# H1N1.net
KiCad netlist of a schematic drawn in Altium Designer
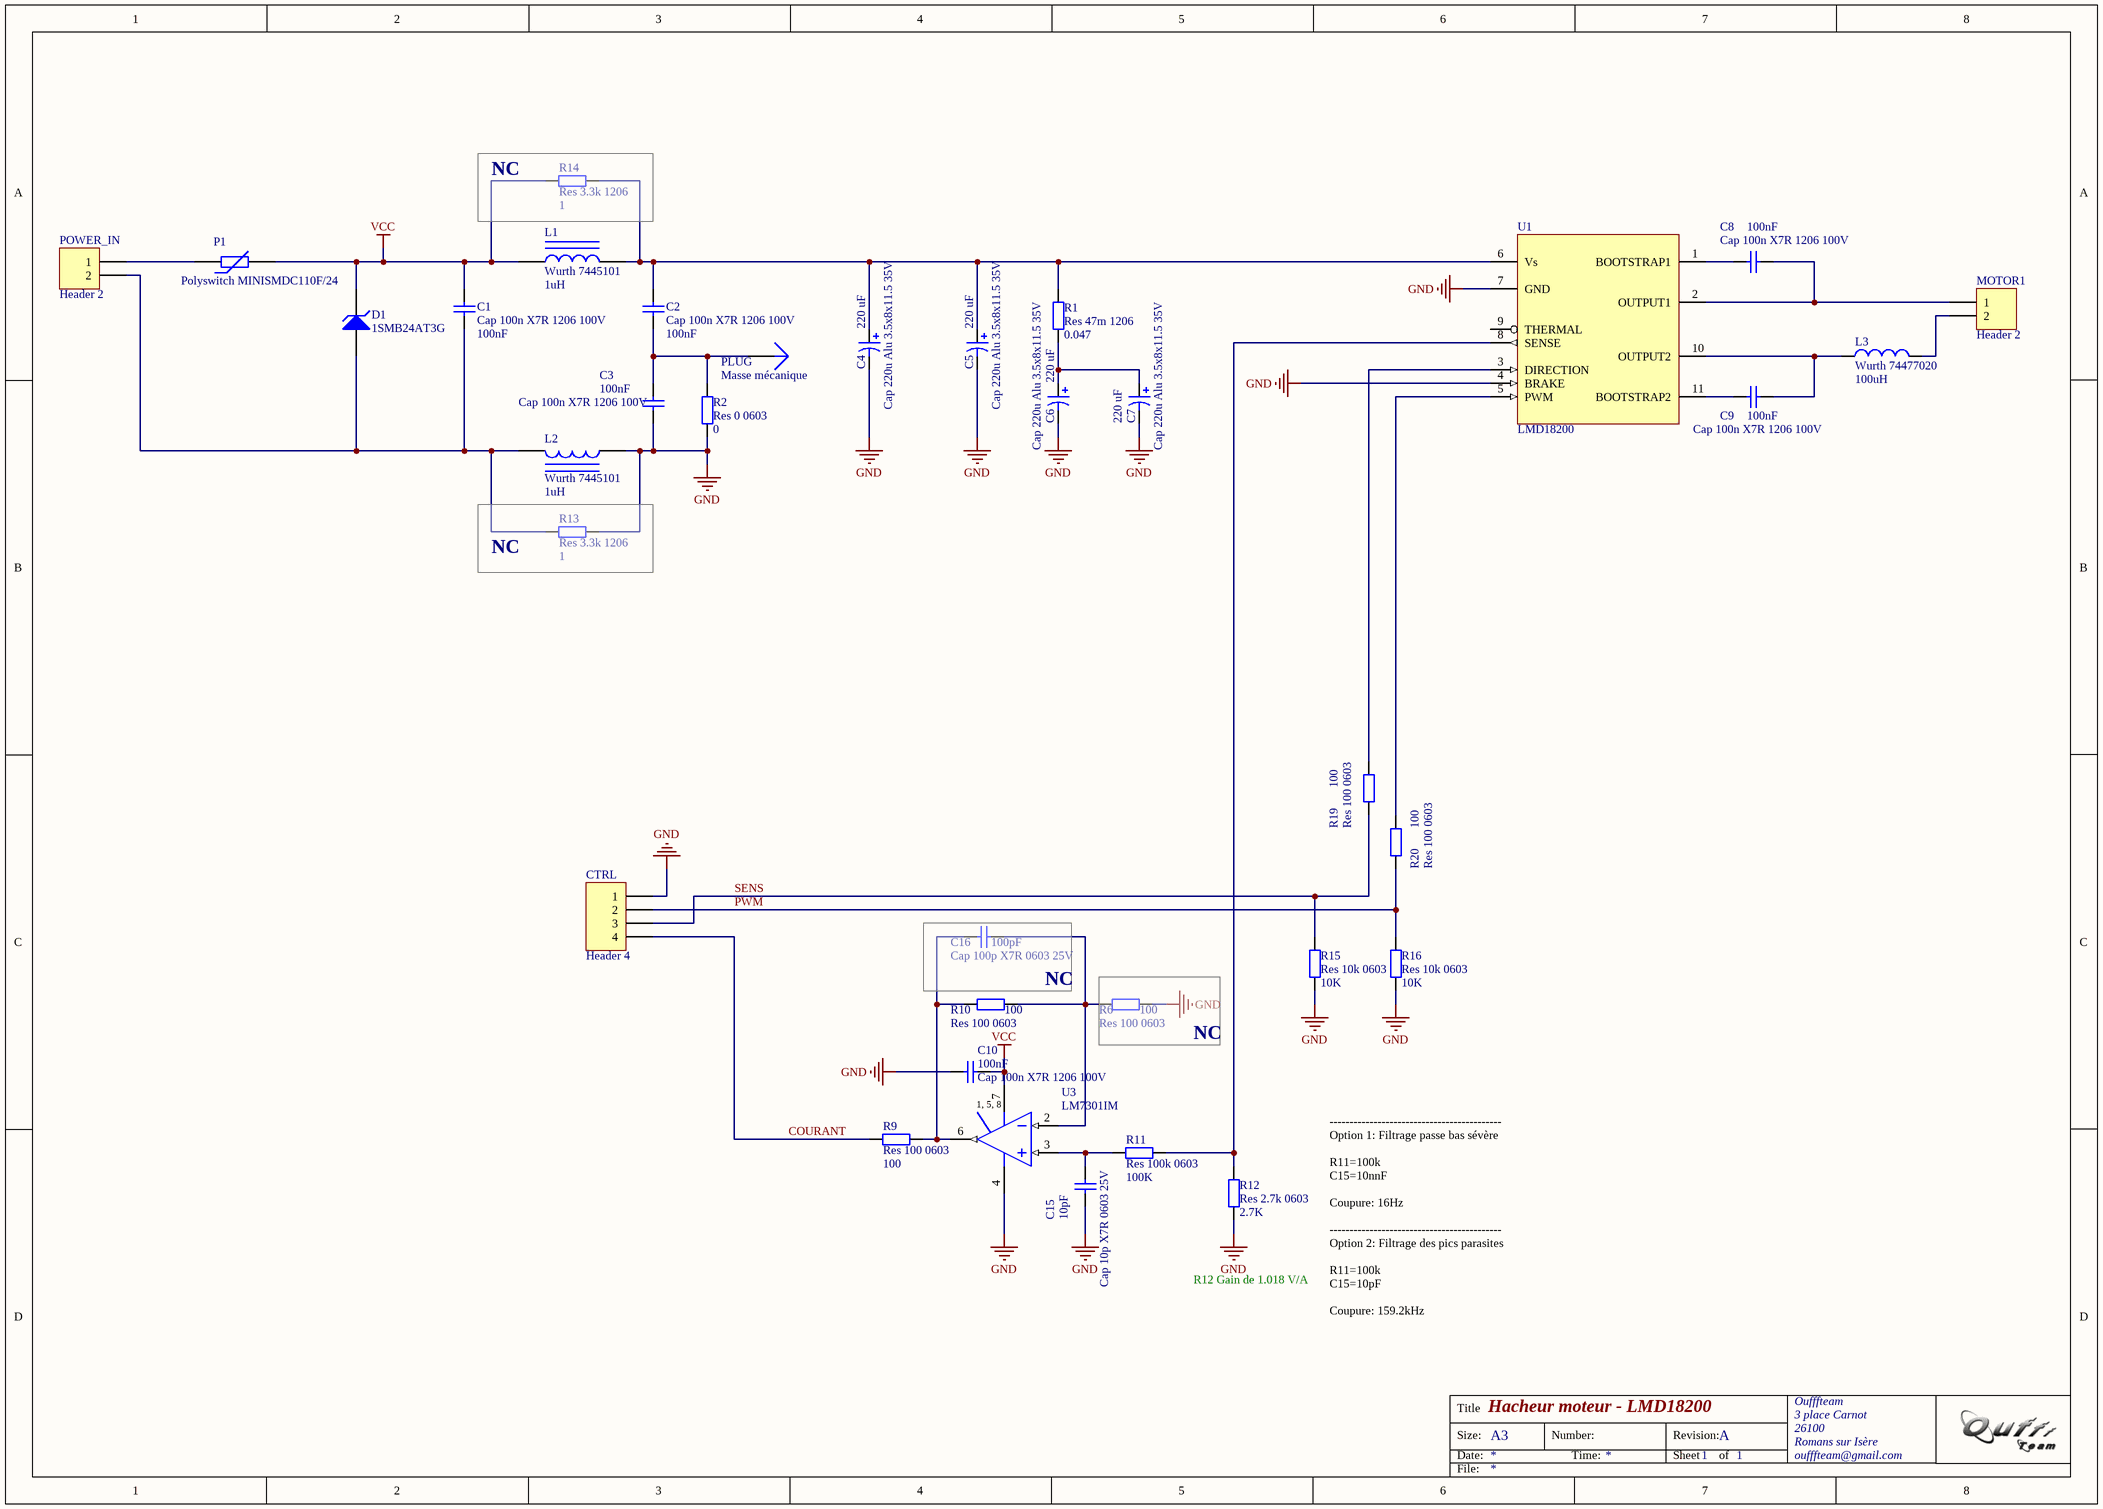
[diagram p0: H1N1.SchDoc]

(export (version "E")
  (design (tool "Eeschema 10.0.6"))
  (components
    (comp (ref "C1")
      (value "Cap 100n X7R 1206 100V")
      (footprint "3216[1206]")
      (description "Capacitor")
      (fields (field (name "ALTIUM_VALUE") "100nF") (field (name "PUBLISHER") "Altium Limited"))
      (libsource (lib "Miscellaneous Devices") (part "Cap"))
    )
    (comp (ref "C2")
      (value "Cap 100n X7R 1206 100V")
      (footprint "3216[1206]")
      (description "Capacitor")
      (fields (field (name "ALTIUM_VALUE") "100nF") (field (name "PUBLISHER") "Altium Limited"))
      (libsource (lib "Miscellaneous Devices") (part "Cap"))
    )
    (comp (ref "C3")
      (value "Cap 100n X7R 1206 100V")
      (footprint "3216[1206]")
      (description "Capacitor")
      (fields (field (name "ALTIUM_VALUE") "100nF") (field (name "PUBLISHER") "Altium Limited"))
      (libsource (lib "Miscellaneous Devices") (part "Cap"))
    )
    (comp (ref "C4")
      (value "Cap 220u Alu 3.5x8x11.5 35V")
      (footprint "CAPPR3.5-8X11.5")
      (description "Polarized Capacitor (Radial)")
      (fields (field (name "ALTIUM_VALUE") "220 uF") (field (name "PUBLISHER") "Altium Limited"))
      (libsource (lib "Miscellaneous Devices") (part "Cap Pol1"))
    )
    (comp (ref "C5")
      (value "Cap 220u Alu 3.5x8x11.5 35V")
      (footprint "CAPPR3.5-8X11.5")
      (description "Polarized Capacitor (Radial)")
      (fields (field (name "ALTIUM_VALUE") "220 uF") (field (name "PUBLISHER") "Altium Limited"))
      (libsource (lib "Miscellaneous Devices") (part "Cap Pol1"))
    )
    (comp (ref "C6")
      (value "Cap 220u Alu 3.5x8x11.5 35V")
      (footprint "CAPPR3.5-8X11.5")
      (description "Polarized Capacitor (Radial)")
      (fields (field (name "ALTIUM_VALUE") "220 uF") (field (name "PUBLISHER") "Altium Limited"))
      (libsource (lib "Miscellaneous Devices") (part "Cap Pol1"))
    )
    (comp (ref "C7")
      (value "Cap 220u Alu 3.5x8x11.5 35V")
      (footprint "CAPPR3.5-8X11.5")
      (description "Polarized Capacitor (Radial)")
      (fields (field (name "ALTIUM_VALUE") "220 uF") (field (name "PUBLISHER") "Altium Limited"))
      (libsource (lib "Miscellaneous Devices") (part "Cap Pol1"))
    )
    (comp (ref "C8")
      (value "Cap 100n X7R 1206 100V")
      (footprint "3216[1206]")
      (description "Capacitor")
      (fields (field (name "ALTIUM_VALUE") "100nF") (field (name "PUBLISHER") "Altium Limited"))
      (libsource (lib "Miscellaneous Devices") (part "Cap"))
    )
    (comp (ref "C9")
      (value "Cap 100n X7R 1206 100V")
      (footprint "3216[1206]")
      (description "Capacitor")
      (fields (field (name "ALTIUM_VALUE") "100nF") (field (name "PUBLISHER") "Altium Limited"))
      (libsource (lib "Miscellaneous Devices") (part "Cap"))
    )
    (comp (ref "C10")
      (value "Cap 100n X7R 1206 100V")
      (footprint "3216[1206]")
      (description "Capacitor")
      (fields (field (name "ALTIUM_VALUE") "100nF") (field (name "PUBLISHER") "Altium Limited"))
      (libsource (lib "Miscellaneous Devices") (part "Cap"))
    )
    (comp (ref "C15")
      (value "Cap 10p X7R 0603 25V")
      (footprint "1608[0603]")
      (description "Capacitor")
      (fields (field (name "ALTIUM_VALUE") "10pF") (field (name "PUBLISHER") "Altium Limited"))
      (libsource (lib "Miscellaneous Devices") (part "Cap"))
    )
    (comp (ref "C16")
      (value "Cap 100p X7R 0603 25V")
      (footprint "1608[0603]")
      (description "Capacitor")
      (fields (field (name "ALTIUM_VALUE") "100pF") (field (name "PUBLISHER") "Altium Limited"))
      (libsource (lib "Miscellaneous Devices") (part "Cap"))
    )
    (comp (ref "CTRL")
      (value "Header 4")
      (footprint "HDR1X4")
      (description "Header, 4-Pin")
      (fields (field (name "PUBLISHER") "Altium Limited"))
      (libsource (lib "Miscellaneous Connectors") (part "Header 4"))
    )
    (comp (ref "D1")
      (value "1SMB24AT3G")
      (footprint "SMB")
      (description "Zener Diode")
      (fields (field (name "PUBLISHER") "Altium Limited"))
      (libsource (lib "Miscellaneous Devices") (part "D Zener"))
    )
    (comp (ref "L1")
      (value "Wurth 7445101")
      (footprint "7445101")
      (description "Magnetic-Core Inductor")
      (fields (field (name "ALTIUM_VALUE") "1uH") (field (name "PUBLISHER") "Altium Limited"))
      (libsource (lib "Miscellaneous Devices") (part "Inductor Iron"))
    )
    (comp (ref "L2")
      (value "Wurth 7445101")
      (footprint "7445101")
      (description "Magnetic-Core Inductor")
      (fields (field (name "ALTIUM_VALUE") "1uH") (field (name "PUBLISHER") "Altium Limited"))
      (libsource (lib "Miscellaneous Devices") (part "Inductor Iron"))
    )
    (comp (ref "L3")
      (value "Wurth 74477020")
      (footprint "74477020")
      (description "Inductor")
      (fields (field (name "ALTIUM_VALUE") "100uH") (field (name "PUBLISHER") "Altium Limited"))
      (libsource (lib "Miscellaneous Devices") (part "Inductor"))
    )
    (comp (ref "MOTOR1")
      (value "Header 2")
      (footprint "Bornier 3.85")
      (description "Header, 2-Pin")
      (fields (field (name "PUBLISHER") "Altium Limited"))
      (libsource (lib "Miscellaneous Connectors") (part "Header 2"))
    )
    (comp (ref "P1")
      (value "Polyswitch MINISMDC110F/24")
      (footprint "1812")
      (description "Varistor (Voltage-Sensitive Resistor)")
      (fields (field (name "PUBLISHER") "Altium Limited"))
      (libsource (lib "Miscellaneous Devices") (part "Res Varistor"))
    )
    (comp (ref "PLUG")
      (value "Masse mécanique")
      (footprint "PIN1")
      (description "Plug")
      (fields (field (name "PUBLISHER") "Altium Limited"))
      (libsource (lib "Miscellaneous Connectors") (part "Plug"))
    )
    (comp (ref "POWER_IN")
      (value "Header 2")
      (footprint "Bornier 3.85")
      (description "Header, 2-Pin")
      (fields (field (name "PUBLISHER") "Altium Limited"))
      (libsource (lib "") (part "Header 2_1"))
    )
    (comp (ref "R1")
      (value "Res 47m 1206")
      (footprint "3216[1206]")
      (description "Resistor")
      (fields (field (name "ALTIUM_VALUE") "0.047") (field (name "PUBLISHER") "Altium Limited"))
      (libsource (lib "") (part "Res2_1"))
    )
    (comp (ref "R2")
      (value "Res 0 0603")
      (footprint "1608[0603]")
      (description "Resistor")
      (fields (field (name "ALTIUM_VALUE") "0") (field (name "PUBLISHER") "Altium Limited"))
      (libsource (lib "") (part "Res2_1"))
    )
    (comp (ref "R6")
      (value "Res 100 0603")
      (footprint "1608[0603]")
      (description "Resistor")
      (fields (field (name "ALTIUM_VALUE") "100") (field (name "PUBLISHER") "Altium Limited"))
      (libsource (lib "Miscellaneous Devices") (part "Res2"))
    )
    (comp (ref "R9")
      (value "Res 100 0603")
      (footprint "1608[0603]")
      (description "Resistor")
      (fields (field (name "ALTIUM_VALUE") "100") (field (name "PUBLISHER") "Altium Limited"))
      (libsource (lib "Miscellaneous Devices") (part "Res2"))
    )
    (comp (ref "R10")
      (value "Res 100 0603")
      (footprint "1608[0603]")
      (description "Resistor")
      (fields (field (name "ALTIUM_VALUE") "100") (field (name "PUBLISHER") "Altium Limited"))
      (libsource (lib "Miscellaneous Devices") (part "Res2"))
    )
    (comp (ref "R11")
      (value "Res 100k 0603")
      (footprint "1608[0603]")
      (description "Resistor")
      (fields (field (name "ALTIUM_VALUE") "100K") (field (name "PUBLISHER") "Altium Limited"))
      (libsource (lib "") (part "Res2_2"))
    )
    (comp (ref "R12")
      (value "Res 2.7k 0603")
      (footprint "1608[0603]")
      (description "Resistor")
      (fields (field (name "ALTIUM_VALUE") "2.7K") (field (name "PUBLISHER") "Altium Limited"))
      (libsource (lib "") (part "Res2_1"))
    )
    (comp (ref "R13")
      (value "Res 3.3k 1206")
      (footprint "3216[1206]")
      (description "Resistor")
      (fields (field (name "ALTIUM_VALUE") "1") (field (name "PUBLISHER") "Altium Limited"))
      (libsource (lib "Miscellaneous Devices") (part "Res2"))
    )
    (comp (ref "R14")
      (value "Res 3.3k 1206")
      (footprint "3216[1206]")
      (description "Resistor")
      (fields (field (name "ALTIUM_VALUE") "1") (field (name "PUBLISHER") "Altium Limited"))
      (libsource (lib "Miscellaneous Devices") (part "Res2"))
    )
    (comp (ref "R15")
      (value "Res 10k 0603")
      (footprint "1608[0603]")
      (description "Resistor")
      (fields (field (name "ALTIUM_VALUE") "10K") (field (name "PUBLISHER") "Altium Limited"))
      (libsource (lib "") (part "Res2_1"))
    )
    (comp (ref "R16")
      (value "Res 10k 0603")
      (footprint "1608[0603]")
      (description "Resistor")
      (fields (field (name "ALTIUM_VALUE") "10K") (field (name "PUBLISHER") "Altium Limited"))
      (libsource (lib "") (part "Res2_1"))
    )
    (comp (ref "R19")
      (value "Res 100 0603")
      (footprint "1608[0603]")
      (description "Resistor")
      (fields (field (name "ALTIUM_VALUE") "100") (field (name "PUBLISHER") "Altium Limited"))
      (libsource (lib "") (part "Res2_1"))
    )
    (comp (ref "R20")
      (value "Res 100 0603")
      (footprint "1608[0603]")
      (description "Resistor")
      (fields (field (name "ALTIUM_VALUE") "100") (field (name "PUBLISHER") "Altium Limited"))
      (libsource (lib "") (part "Res2_1"))
    )
    (comp (ref "U1")
      (value "LMD18200")
      (footprint "LMD18200")
      (description "3A, 55V H-Bridge")
      (libsource (lib "NSC Interface DC Motor Controller Driver") (part "LMD18200"))
    )
    (comp (ref "U3")
      (value "LM7301IM")
      (footprint "M08A_M")
      (description "Low-Power, 4MHZ GBW, Rail-to-Rail Input-Output Operational Amplifier in TinyPak Package")
      (fields (field (name "PUBLISHER") "Altium Limited"))
      (libsource (lib "NSC Operational Amplifier") (part "LM7301IM"))
    )
  )
  (nets
    (net (code "1") (name "/COURANT") (class "Default")
      (node (ref "CTRL") (pin "4") (pinfunction "4_4") (pintype "passive"))
      (node (ref "R9") (pin "1") (pinfunction "1_1") (pintype "passive"))
    )
    (net (code "2") (name "/PWM") (class "Default")
      (node (ref "CTRL") (pin "2") (pinfunction "2_2") (pintype "passive"))
      (node (ref "R16") (pin "2") (pinfunction "2_2") (pintype "passive"))
      (node (ref "R20") (pin "1") (pinfunction "1_1") (pintype "passive"))
    )
    (net (code "3") (name "/SENS") (class "Default")
      (node (ref "CTRL") (pin "3") (pinfunction "3_3") (pintype "passive"))
      (node (ref "R15") (pin "2") (pinfunction "2_2") (pintype "passive"))
      (node (ref "R19") (pin "1") (pinfunction "1_1") (pintype "passive"))
    )
    (net (code "4") (name "GND") (class "Default")
      (node (ref "C10") (pin "1") (pinfunction "1_1") (pintype "passive"))
      (node (ref "C15") (pin "1") (pinfunction "1_1") (pintype "passive"))
      (node (ref "C3") (pin "1") (pinfunction "1_1") (pintype "passive"))
      (node (ref "C4") (pin "2") (pinfunction "2_2") (pintype "passive"))
      (node (ref "C5") (pin "2") (pinfunction "2_2") (pintype "passive"))
      (node (ref "C6") (pin "2") (pinfunction "2_2") (pintype "passive"))
      (node (ref "C7") (pin "2") (pinfunction "2_2") (pintype "passive"))
      (node (ref "CTRL") (pin "1") (pinfunction "1_1") (pintype "passive"))
      (node (ref "L2") (pin "1") (pinfunction "1_1") (pintype "passive"))
      (node (ref "R12") (pin "1") (pinfunction "1_1") (pintype "passive"))
      (node (ref "R13") (pin "2") (pinfunction "2_2") (pintype "passive"))
      (node (ref "R15") (pin "1") (pinfunction "1_1") (pintype "passive"))
      (node (ref "R16") (pin "1") (pinfunction "1_1") (pintype "passive"))
      (node (ref "R2") (pin "1") (pinfunction "1_1") (pintype "passive"))
      (node (ref "R6") (pin "2") (pinfunction "2_2") (pintype "passive"))
      (node (ref "U1") (pin "4") (pinfunction "BRAKE_4") (pintype "input"))
      (node (ref "U1") (pin "7") (pinfunction "GND_7") (pintype "power_in"))
      (node (ref "U3") (pin "4") (pinfunction "V-_4") (pintype "power_in"))
    )
    (net (code "5") (name "Net-(C2-Pad1)") (class "Default")
      (node (ref "C2") (pin "1") (pinfunction "1_1") (pintype "passive"))
      (node (ref "C3") (pin "2") (pinfunction "2_2") (pintype "passive"))
      (node (ref "PLUG") (pin "1") (pinfunction "1_1") (pintype "passive"))
      (node (ref "R2") (pin "2") (pinfunction "2_2") (pintype "passive"))
    )
    (net (code "6") (name "Net-(C6-Pad1)") (class "Default")
      (node (ref "C6") (pin "1") (pinfunction "1_1") (pintype "passive"))
      (node (ref "C7") (pin "1") (pinfunction "1_1") (pintype "passive"))
      (node (ref "R1") (pin "1") (pinfunction "1_1") (pintype "passive"))
    )
    (net (code "7") (name "Net-(D1-A)") (class "Default")
      (node (ref "C1") (pin "1") (pinfunction "1_1") (pintype "passive"))
      (node (ref "D1") (pin "1") (pinfunction "A_1") (pintype "passive"))
      (node (ref "L2") (pin "2") (pinfunction "2_2") (pintype "passive"))
      (node (ref "POWER_IN") (pin "2") (pinfunction "2_2") (pintype "passive"))
      (node (ref "R13") (pin "1") (pinfunction "1_1") (pintype "passive"))
    )
    (net (code "8") (name "Net-(L3-Pad2)") (class "Default")
      (node (ref "L3") (pin "2") (pinfunction "2_2") (pintype "passive"))
      (node (ref "MOTOR1") (pin "2") (pinfunction "2_2") (pintype "passive"))
    )
    (net (code "9") (name "Net-(P1-Pad1)") (class "Default")
      (node (ref "P1") (pin "1") (pinfunction "1_1") (pintype "passive"))
      (node (ref "POWER_IN") (pin "1") (pinfunction "1_1") (pintype "passive"))
    )
    (net (code "10") (name "Net-(U1-BOOTSTRAP1)") (class "Default")
      (node (ref "C8") (pin "1") (pinfunction "1_1") (pintype "passive"))
      (node (ref "U1") (pin "1") (pinfunction "BOOTSTRAP1_1") (pintype "passive"))
    )
    (net (code "11") (name "Net-(U1-BOOTSTRAP2)") (class "Default")
      (node (ref "C9") (pin "1") (pinfunction "1_1") (pintype "passive"))
      (node (ref "U1") (pin "11") (pinfunction "BOOTSTRAP2_11") (pintype "passive"))
    )
    (net (code "12") (name "Net-(U1-DIRECTION)") (class "Default")
      (node (ref "R19") (pin "2") (pinfunction "2_2") (pintype "passive"))
      (node (ref "U1") (pin "3") (pinfunction "DIRECTION_3") (pintype "input"))
    )
    (net (code "13") (name "Net-(U1-OUTPUT1)") (class "Default")
      (node (ref "C8") (pin "2") (pinfunction "2_2") (pintype "passive"))
      (node (ref "MOTOR1") (pin "1") (pinfunction "1_1") (pintype "passive"))
      (node (ref "U1") (pin "2") (pinfunction "OUTPUT1_2") (pintype "power_in"))
    )
    (net (code "14") (name "Net-(U1-OUTPUT2)") (class "Default")
      (node (ref "C9") (pin "2") (pinfunction "2_2") (pintype "passive"))
      (node (ref "L3") (pin "1") (pinfunction "1_1") (pintype "passive"))
      (node (ref "U1") (pin "10") (pinfunction "OUTPUT2_10") (pintype "power_in"))
    )
    (net (code "15") (name "Net-(U1-PWM)") (class "Default")
      (node (ref "R20") (pin "2") (pinfunction "2_2") (pintype "passive"))
      (node (ref "U1") (pin "5") (pinfunction "PWM_5") (pintype "input"))
    )
    (net (code "16") (name "Net-(U1-SENSE)") (class "Default")
      (node (ref "R11") (pin "1") (pinfunction "1_1") (pintype "passive"))
      (node (ref "R12") (pin "2") (pinfunction "2_2") (pintype "passive"))
      (node (ref "U1") (pin "8") (pinfunction "SENSE_8") (pintype "output"))
    )
    (net (code "17") (name "Net-(U1-Vs)") (class "Default")
      (node (ref "C2") (pin "2") (pinfunction "2_2") (pintype "passive"))
      (node (ref "C4") (pin "1") (pinfunction "1_1") (pintype "passive"))
      (node (ref "C5") (pin "1") (pinfunction "1_1") (pintype "passive"))
      (node (ref "L1") (pin "2") (pinfunction "2_2") (pintype "passive"))
      (node (ref "R1") (pin "2") (pinfunction "2_2") (pintype "passive"))
      (node (ref "R14") (pin "2") (pinfunction "2_2") (pintype "passive"))
      (node (ref "U1") (pin "6") (pinfunction "Vs_6") (pintype "power_in"))
    )
    (net (code "18") (name "Net-(U3-IN+)") (class "Default")
      (node (ref "C15") (pin "2") (pinfunction "2_2") (pintype "passive"))
      (node (ref "R11") (pin "2") (pinfunction "2_2") (pintype "passive"))
      (node (ref "U3") (pin "3") (pinfunction "IN+_3") (pintype "input"))
    )
    (net (code "19") (name "Net-(U3-IN-)") (class "Default")
      (node (ref "C16") (pin "2") (pinfunction "2_2") (pintype "passive"))
      (node (ref "R10") (pin "2") (pinfunction "2_2") (pintype "passive"))
      (node (ref "R6") (pin "1") (pinfunction "1_1") (pintype "passive"))
      (node (ref "U3") (pin "2") (pinfunction "IN-_2") (pintype "input"))
    )
    (net (code "20") (name "Net-(U3-OUT)") (class "Default")
      (node (ref "C16") (pin "1") (pinfunction "1_1") (pintype "passive"))
      (node (ref "R10") (pin "1") (pinfunction "1_1") (pintype "passive"))
      (node (ref "R9") (pin "2") (pinfunction "2_2") (pintype "passive"))
      (node (ref "U3") (pin "6") (pinfunction "OUT_6") (pintype "output"))
    )
    (net (code "21") (name "VCC") (class "Default")
      (node (ref "C1") (pin "2") (pinfunction "2_2") (pintype "passive"))
      (node (ref "C10") (pin "2") (pinfunction "2_2") (pintype "passive"))
      (node (ref "D1") (pin "2") (pinfunction "K_2") (pintype "passive"))
      (node (ref "L1") (pin "1") (pinfunction "1_1") (pintype "passive"))
      (node (ref "P1") (pin "2") (pinfunction "2_2") (pintype "passive"))
      (node (ref "R14") (pin "1") (pinfunction "1_1") (pintype "passive"))
      (node (ref "U3") (pin "7") (pinfunction "V+_7") (pintype "power_in"))
    )
    (net (code "22") (name "unconnected-(U1-THERMAL-Pad9)") (class "Default")
      (node (ref "U1") (pin "9") (pinfunction "THERMAL_9") (pintype "open_collector"))
    )
  )
)
